# STM32.net
KiCad netlist of a schematic drawn in Altium Designer
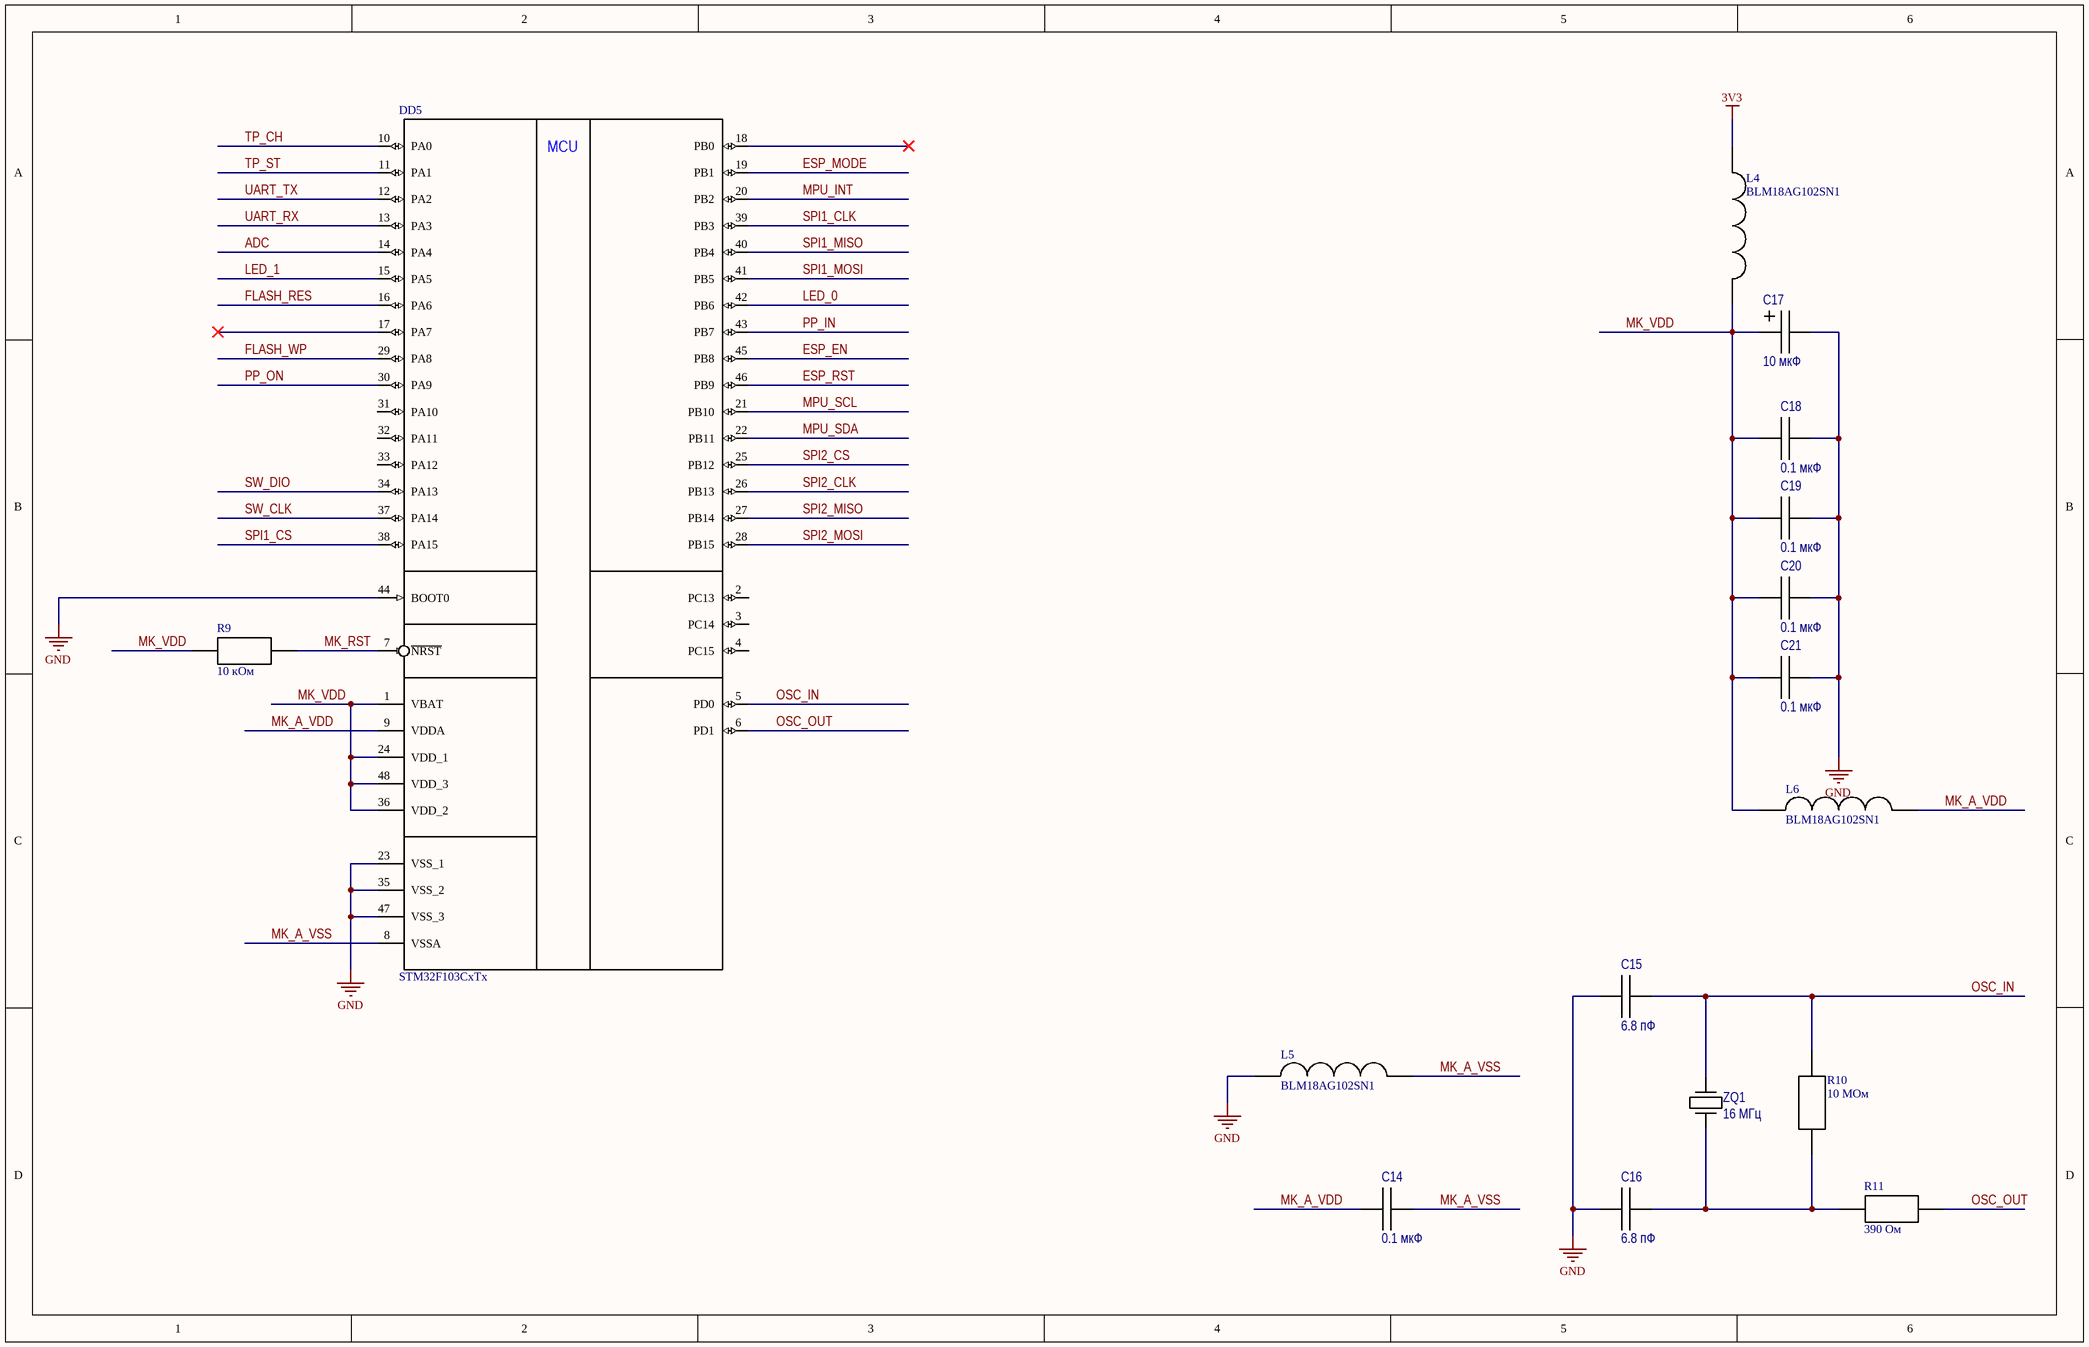
[diagram p0: STM32.SchDoc]

(export (version "E")
  (design (tool "Eeschema 10.0.6"))
  (components
    (comp (ref "C14")
      (value "0.1 мкФ")
      (footprint "C 1206")
      (description "SMD Capacitor 1206")
      (fields
        (field (name "TOLERANCE") "/Укажите допуск в процентах/")
        (field (name "MANUFACTURER") "/Укажите компанию-производителя/")
      )
      (libsource (lib "my_lib") (part "CAP 1206"))
    )
    (comp (ref "C15")
      (value "6.8 пФ")
      (footprint "C 1206")
      (description "SMD Capacitor 1206")
      (fields
        (field (name "TOLERANCE") "/Укажите допуск в процентах/")
        (field (name "MANUFACTURER") "/Укажите компанию-производителя/")
      )
      (libsource (lib "my_lib") (part "CAP 1206"))
    )
    (comp (ref "C16")
      (value "6.8 пФ")
      (footprint "C 1206")
      (description "SMD Capacitor 1206")
      (fields
        (field (name "TOLERANCE") "/Укажите допуск в процентах/")
        (field (name "MANUFACTURER") "/Укажите компанию-производителя/")
      )
      (libsource (lib "my_lib") (part "CAP 1206"))
    )
    (comp (ref "C17")
      (value "10 мкФ")
      (footprint "C TAN_C")
      (description "SMD Tantalium Capacitor C")
      (fields
        (field (name "TOLERANCE") "/Укажите допуск в процентах/")
        (field (name "MANUFACTURER") "/Укажите компанию-производителя/")
      )
      (libsource (lib "my_lib") (part "CAP TAN_C"))
    )
    (comp (ref "C18")
      (value "0.1 мкФ")
      (footprint "C 1206")
      (description "SMD Capacitor 1206")
      (fields
        (field (name "TOLERANCE") "/Укажите допуск в процентах/")
        (field (name "MANUFACTURER") "/Укажите компанию-производителя/")
      )
      (libsource (lib "my_lib") (part "CAP 1206"))
    )
    (comp (ref "C19")
      (value "0.1 мкФ")
      (footprint "C 1206")
      (description "SMD Capacitor 1206")
      (fields
        (field (name "TOLERANCE") "/Укажите допуск в процентах/")
        (field (name "MANUFACTURER") "/Укажите компанию-производителя/")
      )
      (libsource (lib "my_lib") (part "CAP 1206"))
    )
    (comp (ref "C20")
      (value "0.1 мкФ")
      (footprint "C 1206")
      (description "SMD Capacitor 1206")
      (fields
        (field (name "TOLERANCE") "/Укажите допуск в процентах/")
        (field (name "MANUFACTURER") "/Укажите компанию-производителя/")
      )
      (libsource (lib "my_lib") (part "CAP 1206"))
    )
    (comp (ref "C21")
      (value "0.1 мкФ")
      (footprint "C 1206")
      (description "SMD Capacitor 1206")
      (fields
        (field (name "TOLERANCE") "/Укажите допуск в процентах/")
        (field (name "MANUFACTURER") "/Укажите компанию-производителя/")
      )
      (libsource (lib "my_lib") (part "CAP 1206"))
    )
    (comp (ref "DD5")
      (value "STM32F103CxTx")
      (footprint "TSQFP50P900X900X160-48N")
      (libsource (lib "my_lib") (part "STM32F103CxTx"))
    )
    (comp (ref "L4")
      (value "BLM18AG102SN1")
      (footprint "FB 0603")
      (libsource (lib "my_lib") (part "BLM18AG102SN1"))
    )
    (comp (ref "L5")
      (value "BLM18AG102SN1")
      (footprint "FB 0603")
      (libsource (lib "my_lib") (part "BLM18AG102SN1"))
    )
    (comp (ref "L6")
      (value "BLM18AG102SN1")
      (footprint "FB 0603")
      (libsource (lib "my_lib") (part "BLM18AG102SN1"))
    )
    (comp (ref "R9") (value "10 кОм") (footprint "RES 0805") (libsource (lib "my_lib") (part "RES 0805")))
    (comp (ref "R10") (value "10 МОм") (footprint "RES 0805") (libsource (lib "my_lib") (part "RES 0805")))
    (comp (ref "R11") (value "390 Ом") (footprint "RES 0805") (libsource (lib "my_lib") (part "RES 0805")))
    (comp (ref "ZQ1")
      (value "16 МГц")
      (footprint "NX3225SA")
      (description "QUARTZ CRYSTAL")
      (fields (field (name "MANUFACTURER") "NDK") (field (name "Comment") "NX3225SA-16.000M-STD-CRS-2"))
      (libsource (lib "my_lib") (part "NX3225SA-16.000M-STD-CRS-2"))
    )
  )
  (nets
    (net (code "1") (name "/ADC") (class "Default")
      (node (ref "DD5") (pin "14") (pinfunction "PA4_14") (pintype "bidirectional"))
    )
    (net (code "2") (name "/ESP_EN") (class "Default")
      (node (ref "DD5") (pin "45") (pinfunction "PB8_45") (pintype "bidirectional"))
    )
    (net (code "3") (name "/ESP_MODE") (class "Default")
      (node (ref "DD5") (pin "19") (pinfunction "PB1_19") (pintype "bidirectional"))
    )
    (net (code "4") (name "/ESP_RST") (class "Default")
      (node (ref "DD5") (pin "46") (pinfunction "PB9_46") (pintype "bidirectional"))
    )
    (net (code "5") (name "/FLASH_RES") (class "Default")
      (node (ref "DD5") (pin "16") (pinfunction "PA6_16") (pintype "bidirectional"))
    )
    (net (code "6") (name "/FLASH_WP") (class "Default")
      (node (ref "DD5") (pin "29") (pinfunction "PA8_29") (pintype "bidirectional"))
    )
    (net (code "7") (name "/LED_0") (class "Default")
      (node (ref "DD5") (pin "42") (pinfunction "PB6_42") (pintype "bidirectional"))
    )
    (net (code "8") (name "/LED_1") (class "Default")
      (node (ref "DD5") (pin "15") (pinfunction "PA5_15") (pintype "bidirectional"))
    )
    (net (code "9") (name "/MK_A_VDD") (class "Default")
      (node (ref "C14") (pin "1") (pinfunction "1_1") (pintype "passive"))
      (node (ref "DD5") (pin "9") (pinfunction "VDDA_9") (pintype "power_in"))
      (node (ref "L6") (pin "2") (pinfunction "2_2") (pintype "passive"))
    )
    (net (code "10") (name "/MK_A_VSS") (class "Default")
      (node (ref "C14") (pin "2") (pinfunction "2_2") (pintype "passive"))
      (node (ref "DD5") (pin "8") (pinfunction "VSSA_8") (pintype "power_in"))
      (node (ref "L5") (pin "2") (pinfunction "2_2") (pintype "passive"))
    )
    (net (code "11") (name "/MK_RST") (class "Default")
      (node (ref "DD5") (pin "7") (pinfunction "~{NRST}_7") (pintype "input"))
      (node (ref "R9") (pin "1") (pinfunction "1_1") (pintype "passive"))
    )
    (net (code "12") (name "/MK_VDD") (class "Default")
      (node (ref "C17") (pin "1") (pinfunction "1_1") (pintype "passive"))
      (node (ref "C18") (pin "1") (pinfunction "1_1") (pintype "passive"))
      (node (ref "C19") (pin "1") (pinfunction "1_1") (pintype "passive"))
      (node (ref "C20") (pin "1") (pinfunction "1_1") (pintype "passive"))
      (node (ref "C21") (pin "1") (pinfunction "1_1") (pintype "passive"))
      (node (ref "DD5") (pin "1") (pinfunction "VBAT_1") (pintype "power_in"))
      (node (ref "DD5") (pin "24") (pinfunction "VDD_1_24") (pintype "power_in"))
      (node (ref "DD5") (pin "36") (pinfunction "VDD_2_36") (pintype "power_in"))
      (node (ref "DD5") (pin "48") (pinfunction "VDD_3_48") (pintype "power_in"))
      (node (ref "L4") (pin "2") (pinfunction "2_2") (pintype "passive"))
      (node (ref "L6") (pin "1") (pinfunction "1_1") (pintype "passive"))
      (node (ref "R9") (pin "2") (pinfunction "2_2") (pintype "passive"))
    )
    (net (code "13") (name "/MPU_INT") (class "Default")
      (node (ref "DD5") (pin "20") (pinfunction "PB2_20") (pintype "bidirectional"))
    )
    (net (code "14") (name "/MPU_SCL") (class "Default")
      (node (ref "DD5") (pin "21") (pinfunction "PB10_21") (pintype "bidirectional"))
    )
    (net (code "15") (name "/MPU_SDA") (class "Default")
      (node (ref "DD5") (pin "22") (pinfunction "PB11_22") (pintype "bidirectional"))
    )
    (net (code "16") (name "/OSC_IN") (class "Default")
      (node (ref "C15") (pin "2") (pinfunction "2_2") (pintype "passive"))
      (node (ref "DD5") (pin "5") (pinfunction "PD0_5") (pintype "bidirectional"))
      (node (ref "R10") (pin "2") (pinfunction "2_2") (pintype "passive"))
      (node (ref "ZQ1") (pin "3") (pinfunction "XO_3") (pintype "passive"))
    )
    (net (code "17") (name "/OSC_OUT") (class "Default")
      (node (ref "DD5") (pin "6") (pinfunction "PD1_6") (pintype "bidirectional"))
      (node (ref "R11") (pin "2") (pinfunction "2_2") (pintype "passive"))
    )
    (net (code "18") (name "/PP_IN") (class "Default")
      (node (ref "DD5") (pin "43") (pinfunction "PB7_43") (pintype "bidirectional"))
    )
    (net (code "19") (name "/PP_ON") (class "Default")
      (node (ref "DD5") (pin "30") (pinfunction "PA9_30") (pintype "bidirectional"))
    )
    (net (code "20") (name "/SPI1_CLK") (class "Default")
      (node (ref "DD5") (pin "39") (pinfunction "PB3_39") (pintype "bidirectional"))
    )
    (net (code "21") (name "/SPI1_CS") (class "Default")
      (node (ref "DD5") (pin "38") (pinfunction "PA15_38") (pintype "bidirectional"))
    )
    (net (code "22") (name "/SPI1_MISO") (class "Default")
      (node (ref "DD5") (pin "40") (pinfunction "PB4_40") (pintype "bidirectional"))
    )
    (net (code "23") (name "/SPI1_MOSI") (class "Default")
      (node (ref "DD5") (pin "41") (pinfunction "PB5_41") (pintype "bidirectional"))
    )
    (net (code "24") (name "/SPI2_CLK") (class "Default")
      (node (ref "DD5") (pin "26") (pinfunction "PB13_26") (pintype "bidirectional"))
    )
    (net (code "25") (name "/SPI2_CS") (class "Default")
      (node (ref "DD5") (pin "25") (pinfunction "PB12_25") (pintype "bidirectional"))
    )
    (net (code "26") (name "/SPI2_MISO") (class "Default")
      (node (ref "DD5") (pin "27") (pinfunction "PB14_27") (pintype "bidirectional"))
    )
    (net (code "27") (name "/SPI2_MOSI") (class "Default")
      (node (ref "DD5") (pin "28") (pinfunction "PB15_28") (pintype "bidirectional"))
    )
    (net (code "28") (name "/SW_CLK") (class "Default")
      (node (ref "DD5") (pin "37") (pinfunction "PA14_37") (pintype "bidirectional"))
    )
    (net (code "29") (name "/SW_DIO") (class "Default")
      (node (ref "DD5") (pin "34") (pinfunction "PA13_34") (pintype "bidirectional"))
    )
    (net (code "30") (name "/TP_CH") (class "Default")
      (node (ref "DD5") (pin "10") (pinfunction "PA0_10") (pintype "bidirectional"))
    )
    (net (code "31") (name "/TP_ST") (class "Default")
      (node (ref "DD5") (pin "11") (pinfunction "PA1_11") (pintype "bidirectional"))
    )
    (net (code "32") (name "/UART_RX") (class "Default")
      (node (ref "DD5") (pin "13") (pinfunction "PA3_13") (pintype "bidirectional"))
    )
    (net (code "33") (name "/UART_TX") (class "Default")
      (node (ref "DD5") (pin "12") (pinfunction "PA2_12") (pintype "bidirectional"))
    )
    (net (code "34") (name "3V3") (class "Default")
      (node (ref "L4") (pin "1") (pinfunction "1_1") (pintype "passive"))
    )
    (net (code "35") (name "GND") (class "Default")
      (node (ref "C15") (pin "1") (pinfunction "1_1") (pintype "passive"))
      (node (ref "C16") (pin "1") (pinfunction "1_1") (pintype "passive"))
      (node (ref "C17") (pin "2") (pinfunction "2_2") (pintype "passive"))
      (node (ref "C18") (pin "2") (pinfunction "2_2") (pintype "passive"))
      (node (ref "C19") (pin "2") (pinfunction "2_2") (pintype "passive"))
      (node (ref "C20") (pin "2") (pinfunction "2_2") (pintype "passive"))
      (node (ref "C21") (pin "2") (pinfunction "2_2") (pintype "passive"))
      (node (ref "DD5") (pin "23") (pinfunction "VSS_1_23") (pintype "power_in"))
      (node (ref "DD5") (pin "35") (pinfunction "VSS_2_35") (pintype "power_in"))
      (node (ref "DD5") (pin "44") (pinfunction "BOOT0_44") (pintype "input"))
      (node (ref "DD5") (pin "47") (pinfunction "VSS_3_47") (pintype "power_in"))
      (node (ref "L5") (pin "1") (pinfunction "1_1") (pintype "passive"))
    )
    (net (code "36") (name "Net-(ZQ1-XI)") (class "Default")
      (node (ref "C16") (pin "2") (pinfunction "2_2") (pintype "passive"))
      (node (ref "R10") (pin "1") (pinfunction "1_1") (pintype "passive"))
      (node (ref "R11") (pin "1") (pinfunction "1_1") (pintype "passive"))
      (node (ref "ZQ1") (pin "1") (pinfunction "XI_1") (pintype "passive"))
    )
    (net (code "37") (name "unconnected-(DD5-PA7-Pad17)") (class "Default")
      (node (ref "DD5") (pin "17") (pinfunction "PA7_17") (pintype "bidirectional+no_connect"))
    )
    (net (code "38") (name "unconnected-(DD5-PA10-Pad31)") (class "Default")
      (node (ref "DD5") (pin "31") (pinfunction "PA10_31") (pintype "bidirectional"))
    )
    (net (code "39") (name "unconnected-(DD5-PA11-Pad32)") (class "Default")
      (node (ref "DD5") (pin "32") (pinfunction "PA11_32") (pintype "bidirectional"))
    )
    (net (code "40") (name "unconnected-(DD5-PA12-Pad33)") (class "Default")
      (node (ref "DD5") (pin "33") (pinfunction "PA12_33") (pintype "bidirectional"))
    )
    (net (code "41") (name "unconnected-(DD5-PB0-Pad18)") (class "Default")
      (node (ref "DD5") (pin "18") (pinfunction "PB0_18") (pintype "bidirectional+no_connect"))
    )
    (net (code "42") (name "unconnected-(DD5-PC13-Pad2)") (class "Default")
      (node (ref "DD5") (pin "2") (pinfunction "PC13_2") (pintype "bidirectional"))
    )
    (net (code "43") (name "unconnected-(DD5-PC14-Pad3)") (class "Default")
      (node (ref "DD5") (pin "3") (pinfunction "PC14_3") (pintype "bidirectional"))
    )
    (net (code "44") (name "unconnected-(DD5-PC15-Pad4)") (class "Default")
      (node (ref "DD5") (pin "4") (pinfunction "PC15_4") (pintype "bidirectional"))
    )
    (net (code "45") (name "unconnected-(ZQ1-NC-Pad2)") (class "Default")
      (node (ref "ZQ1") (pin "2") (pinfunction "NC_2") (pintype "passive"))
    )
    (net (code "46") (name "unconnected-(ZQ1-NC-Pad4)") (class "Default")
      (node (ref "ZQ1") (pin "4") (pinfunction "NC_4") (pintype "passive"))
    )
  )
)
